# Unbricker.net
KiCad netlist of a schematic drawn in EAGLE
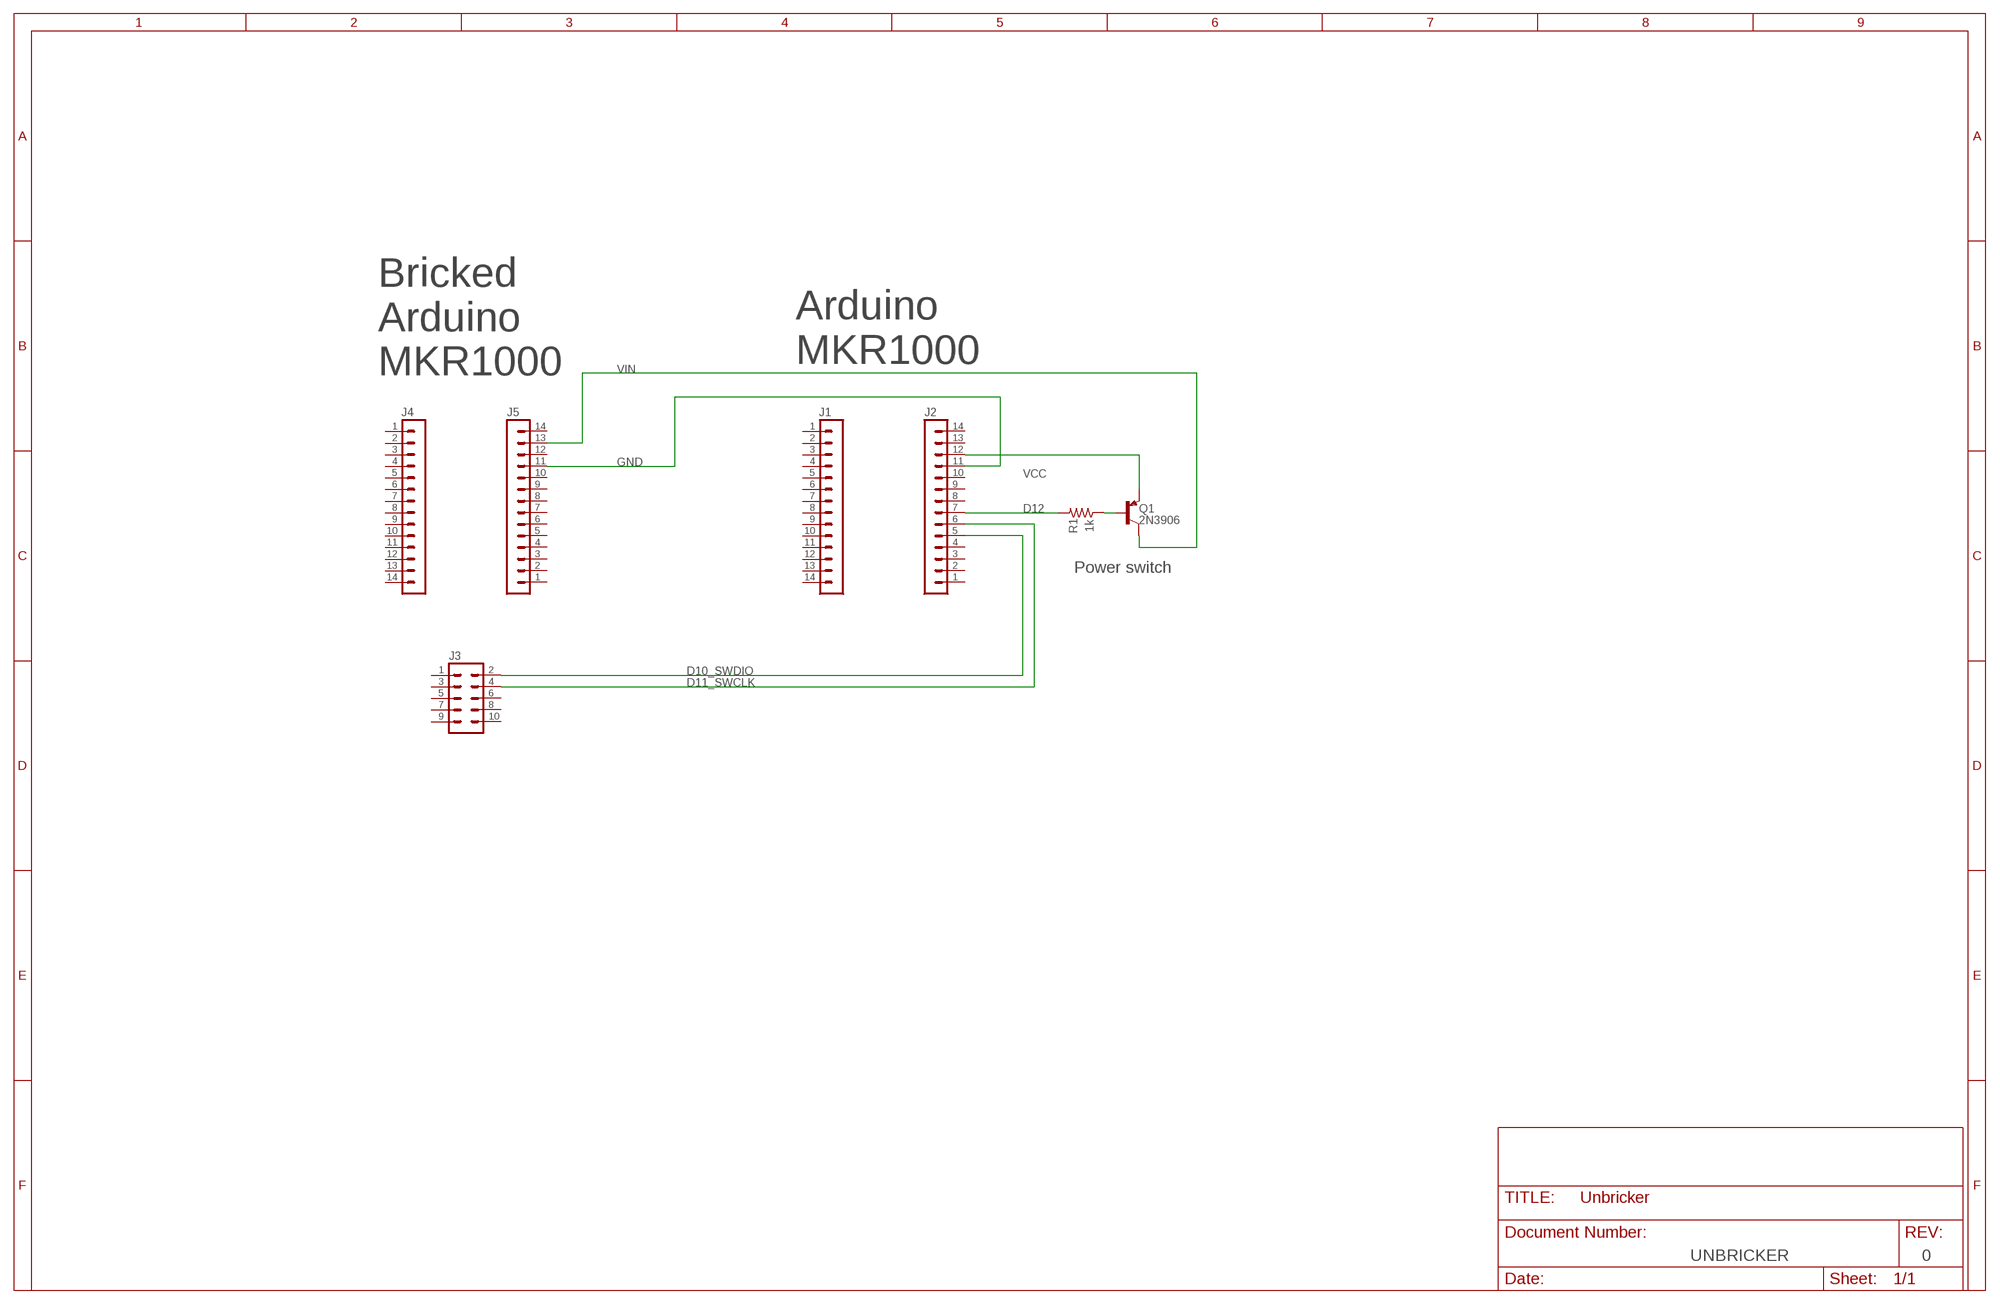
[diagram p0: schematic, sheet 1]

(export (version "E")
  (design (tool "Eeschema 10.0.6"))
  (components
    (comp (ref "J1")
      (value "MA14-1")
      (footprint "eagle-import:MA14-1")
      (libsource (lib "eagle-import") (part "MA14-1"))
    )
    (comp (ref "J2")
      (value "MA14-1")
      (footprint "eagle-import:MA14-1")
      (libsource (lib "eagle-import") (part "MA14-1"))
    )
    (comp (ref "J3")
      (value "M50-3600542")
      (footprint "eagle-import:FCI-MINITEK127HDR-10")
      (fields (field (name "MF") "Harwin") (field (name "MPN") "M50-3600542 "))
      (libsource (lib "eagle-import") (part "M50-3600542"))
    )
    (comp (ref "J4")
      (value "MA14-1")
      (footprint "eagle-import:MA14-1")
      (libsource (lib "eagle-import") (part "MA14-1"))
    )
    (comp (ref "J5")
      (value "MA14-1")
      (footprint "eagle-import:MA14-1")
      (libsource (lib "eagle-import") (part "MA14-1"))
    )
    (comp (ref "Q1")
      (value "2N3906")
      (footprint "eagle-import:SOT23")
      (fields (field (name "MF") "FAIRCHILD") (field (name "MPN") "MMBT3906"))
      (libsource (lib "eagle-import") (part "PNPMMBT3906"))
    )
    (comp (ref "R1")
      (value "1k")
      (footprint "eagle-import:R0603")
      (libsource (lib "eagle-import") (part "RB"))
    )
  )
  (nets
    (net (code "1") (name "/D10_SWDIO") (class "Default")
      (node (ref "J2") (pin "5") (pinfunction "5_5") (pintype "passive"))
      (node (ref "J3") (pin "2") (pinfunction "2_2") (pintype "passive"))
    )
    (net (code "2") (name "/D11_SWCLK") (class "Default")
      (node (ref "J2") (pin "6") (pinfunction "6_6") (pintype "passive"))
      (node (ref "J3") (pin "4") (pinfunction "4_4") (pintype "passive"))
    )
    (net (code "3") (name "/D12") (class "Default")
      (node (ref "J2") (pin "7") (pinfunction "7_7") (pintype "passive"))
      (node (ref "R1") (pin "2") (pinfunction "2_2") (pintype "passive"))
    )
    (net (code "4") (name "/GND") (class "Default")
      (node (ref "J2") (pin "11") (pinfunction "11_11") (pintype "passive"))
      (node (ref "J5") (pin "11") (pinfunction "11_11") (pintype "passive"))
    )
    (net (code "5") (name "/VCC") (class "Default")
      (node (ref "J2") (pin "12") (pinfunction "12_12") (pintype "passive"))
      (node (ref "Q1") (pin "3") (pinfunction "E_3") (pintype "passive"))
    )
    (net (code "6") (name "/VIN") (class "Default")
      (node (ref "J5") (pin "13") (pinfunction "13_13") (pintype "passive"))
      (node (ref "Q1") (pin "2") (pinfunction "C_2") (pintype "passive"))
    )
    (net (code "7") (name "Net-(Q1-B)") (class "Default")
      (node (ref "Q1") (pin "1") (pinfunction "B_1") (pintype "passive"))
      (node (ref "R1") (pin "1") (pinfunction "1_1") (pintype "passive"))
    )
    (net (code "8") (name "unconnected-(J1-Pad1)") (class "Default")
      (node (ref "J1") (pin "1") (pinfunction "1_1") (pintype "passive"))
    )
    (net (code "9") (name "unconnected-(J1-Pad2)") (class "Default")
      (node (ref "J1") (pin "2") (pinfunction "2_2") (pintype "passive"))
    )
    (net (code "10") (name "unconnected-(J1-Pad3)") (class "Default")
      (node (ref "J1") (pin "3") (pinfunction "3_3") (pintype "passive"))
    )
    (net (code "11") (name "unconnected-(J1-Pad4)") (class "Default")
      (node (ref "J1") (pin "4") (pinfunction "4_4") (pintype "passive"))
    )
    (net (code "12") (name "unconnected-(J1-Pad5)") (class "Default")
      (node (ref "J1") (pin "5") (pinfunction "5_5") (pintype "passive"))
    )
    (net (code "13") (name "unconnected-(J1-Pad6)") (class "Default")
      (node (ref "J1") (pin "6") (pinfunction "6_6") (pintype "passive"))
    )
    (net (code "14") (name "unconnected-(J1-Pad7)") (class "Default")
      (node (ref "J1") (pin "7") (pinfunction "7_7") (pintype "passive"))
    )
    (net (code "15") (name "unconnected-(J1-Pad8)") (class "Default")
      (node (ref "J1") (pin "8") (pinfunction "8_8") (pintype "passive"))
    )
    (net (code "16") (name "unconnected-(J1-Pad9)") (class "Default")
      (node (ref "J1") (pin "9") (pinfunction "9_9") (pintype "passive"))
    )
    (net (code "17") (name "unconnected-(J1-Pad10)") (class "Default")
      (node (ref "J1") (pin "10") (pinfunction "10_10") (pintype "passive"))
    )
    (net (code "18") (name "unconnected-(J1-Pad11)") (class "Default")
      (node (ref "J1") (pin "11") (pinfunction "11_11") (pintype "passive"))
    )
    (net (code "19") (name "unconnected-(J1-Pad12)") (class "Default")
      (node (ref "J1") (pin "12") (pinfunction "12_12") (pintype "passive"))
    )
    (net (code "20") (name "unconnected-(J1-Pad13)") (class "Default")
      (node (ref "J1") (pin "13") (pinfunction "13_13") (pintype "passive"))
    )
    (net (code "21") (name "unconnected-(J1-Pad14)") (class "Default")
      (node (ref "J1") (pin "14") (pinfunction "14_14") (pintype "passive"))
    )
    (net (code "22") (name "unconnected-(J2-Pad1)") (class "Default")
      (node (ref "J2") (pin "1") (pinfunction "1_1") (pintype "passive"))
    )
    (net (code "23") (name "unconnected-(J2-Pad2)") (class "Default")
      (node (ref "J2") (pin "2") (pinfunction "2_2") (pintype "passive"))
    )
    (net (code "24") (name "unconnected-(J2-Pad3)") (class "Default")
      (node (ref "J2") (pin "3") (pinfunction "3_3") (pintype "passive"))
    )
    (net (code "25") (name "unconnected-(J2-Pad4)") (class "Default")
      (node (ref "J2") (pin "4") (pinfunction "4_4") (pintype "passive"))
    )
    (net (code "26") (name "unconnected-(J2-Pad8)") (class "Default")
      (node (ref "J2") (pin "8") (pinfunction "8_8") (pintype "passive"))
    )
    (net (code "27") (name "unconnected-(J2-Pad9)") (class "Default")
      (node (ref "J2") (pin "9") (pinfunction "9_9") (pintype "passive"))
    )
    (net (code "28") (name "unconnected-(J2-Pad10)") (class "Default")
      (node (ref "J2") (pin "10") (pinfunction "10_10") (pintype "passive"))
    )
    (net (code "29") (name "unconnected-(J2-Pad13)") (class "Default")
      (node (ref "J2") (pin "13") (pinfunction "13_13") (pintype "passive"))
    )
    (net (code "30") (name "unconnected-(J2-Pad14)") (class "Default")
      (node (ref "J2") (pin "14") (pinfunction "14_14") (pintype "passive"))
    )
    (net (code "31") (name "unconnected-(J3-Pad1)") (class "Default")
      (node (ref "J3") (pin "1") (pinfunction "1_1") (pintype "passive"))
    )
    (net (code "32") (name "unconnected-(J3-Pad3)") (class "Default")
      (node (ref "J3") (pin "3") (pinfunction "3_3") (pintype "passive"))
    )
    (net (code "33") (name "unconnected-(J3-Pad5)") (class "Default")
      (node (ref "J3") (pin "5") (pinfunction "5_5") (pintype "passive"))
    )
    (net (code "34") (name "unconnected-(J3-Pad6)") (class "Default")
      (node (ref "J3") (pin "6") (pinfunction "6_6") (pintype "passive"))
    )
    (net (code "35") (name "unconnected-(J3-Pad7)") (class "Default")
      (node (ref "J3") (pin "7") (pinfunction "7_7") (pintype "passive"))
    )
    (net (code "36") (name "unconnected-(J3-Pad8)") (class "Default")
      (node (ref "J3") (pin "8") (pinfunction "8_8") (pintype "passive"))
    )
    (net (code "37") (name "unconnected-(J3-Pad9)") (class "Default")
      (node (ref "J3") (pin "9") (pinfunction "9_9") (pintype "passive"))
    )
    (net (code "38") (name "unconnected-(J3-Pad10)") (class "Default")
      (node (ref "J3") (pin "10") (pinfunction "10_10") (pintype "passive"))
    )
    (net (code "39") (name "unconnected-(J4-Pad1)") (class "Default")
      (node (ref "J4") (pin "1") (pinfunction "1_1") (pintype "passive"))
    )
    (net (code "40") (name "unconnected-(J4-Pad2)") (class "Default")
      (node (ref "J4") (pin "2") (pinfunction "2_2") (pintype "passive"))
    )
    (net (code "41") (name "unconnected-(J4-Pad3)") (class "Default")
      (node (ref "J4") (pin "3") (pinfunction "3_3") (pintype "passive"))
    )
    (net (code "42") (name "unconnected-(J4-Pad4)") (class "Default")
      (node (ref "J4") (pin "4") (pinfunction "4_4") (pintype "passive"))
    )
    (net (code "43") (name "unconnected-(J4-Pad5)") (class "Default")
      (node (ref "J4") (pin "5") (pinfunction "5_5") (pintype "passive"))
    )
    (net (code "44") (name "unconnected-(J4-Pad6)") (class "Default")
      (node (ref "J4") (pin "6") (pinfunction "6_6") (pintype "passive"))
    )
    (net (code "45") (name "unconnected-(J4-Pad7)") (class "Default")
      (node (ref "J4") (pin "7") (pinfunction "7_7") (pintype "passive"))
    )
    (net (code "46") (name "unconnected-(J4-Pad8)") (class "Default")
      (node (ref "J4") (pin "8") (pinfunction "8_8") (pintype "passive"))
    )
    (net (code "47") (name "unconnected-(J4-Pad9)") (class "Default")
      (node (ref "J4") (pin "9") (pinfunction "9_9") (pintype "passive"))
    )
    (net (code "48") (name "unconnected-(J4-Pad10)") (class "Default")
      (node (ref "J4") (pin "10") (pinfunction "10_10") (pintype "passive"))
    )
    (net (code "49") (name "unconnected-(J4-Pad11)") (class "Default")
      (node (ref "J4") (pin "11") (pinfunction "11_11") (pintype "passive"))
    )
    (net (code "50") (name "unconnected-(J4-Pad12)") (class "Default")
      (node (ref "J4") (pin "12") (pinfunction "12_12") (pintype "passive"))
    )
    (net (code "51") (name "unconnected-(J4-Pad13)") (class "Default")
      (node (ref "J4") (pin "13") (pinfunction "13_13") (pintype "passive"))
    )
    (net (code "52") (name "unconnected-(J4-Pad14)") (class "Default")
      (node (ref "J4") (pin "14") (pinfunction "14_14") (pintype "passive"))
    )
    (net (code "53") (name "unconnected-(J5-Pad1)") (class "Default")
      (node (ref "J5") (pin "1") (pinfunction "1_1") (pintype "passive"))
    )
    (net (code "54") (name "unconnected-(J5-Pad2)") (class "Default")
      (node (ref "J5") (pin "2") (pinfunction "2_2") (pintype "passive"))
    )
    (net (code "55") (name "unconnected-(J5-Pad3)") (class "Default")
      (node (ref "J5") (pin "3") (pinfunction "3_3") (pintype "passive"))
    )
    (net (code "56") (name "unconnected-(J5-Pad4)") (class "Default")
      (node (ref "J5") (pin "4") (pinfunction "4_4") (pintype "passive"))
    )
    (net (code "57") (name "unconnected-(J5-Pad5)") (class "Default")
      (node (ref "J5") (pin "5") (pinfunction "5_5") (pintype "passive"))
    )
    (net (code "58") (name "unconnected-(J5-Pad6)") (class "Default")
      (node (ref "J5") (pin "6") (pinfunction "6_6") (pintype "passive"))
    )
    (net (code "59") (name "unconnected-(J5-Pad7)") (class "Default")
      (node (ref "J5") (pin "7") (pinfunction "7_7") (pintype "passive"))
    )
    (net (code "60") (name "unconnected-(J5-Pad8)") (class "Default")
      (node (ref "J5") (pin "8") (pinfunction "8_8") (pintype "passive"))
    )
    (net (code "61") (name "unconnected-(J5-Pad9)") (class "Default")
      (node (ref "J5") (pin "9") (pinfunction "9_9") (pintype "passive"))
    )
    (net (code "62") (name "unconnected-(J5-Pad10)") (class "Default")
      (node (ref "J5") (pin "10") (pinfunction "10_10") (pintype "passive"))
    )
    (net (code "63") (name "unconnected-(J5-Pad12)") (class "Default")
      (node (ref "J5") (pin "12") (pinfunction "12_12") (pintype "passive"))
    )
    (net (code "64") (name "unconnected-(J5-Pad14)") (class "Default")
      (node (ref "J5") (pin "14") (pinfunction "14_14") (pintype "passive"))
    )
  )
)
